# DISPLAYPORT_USBC.net
KiCad netlist of a schematic drawn in Altium Designer
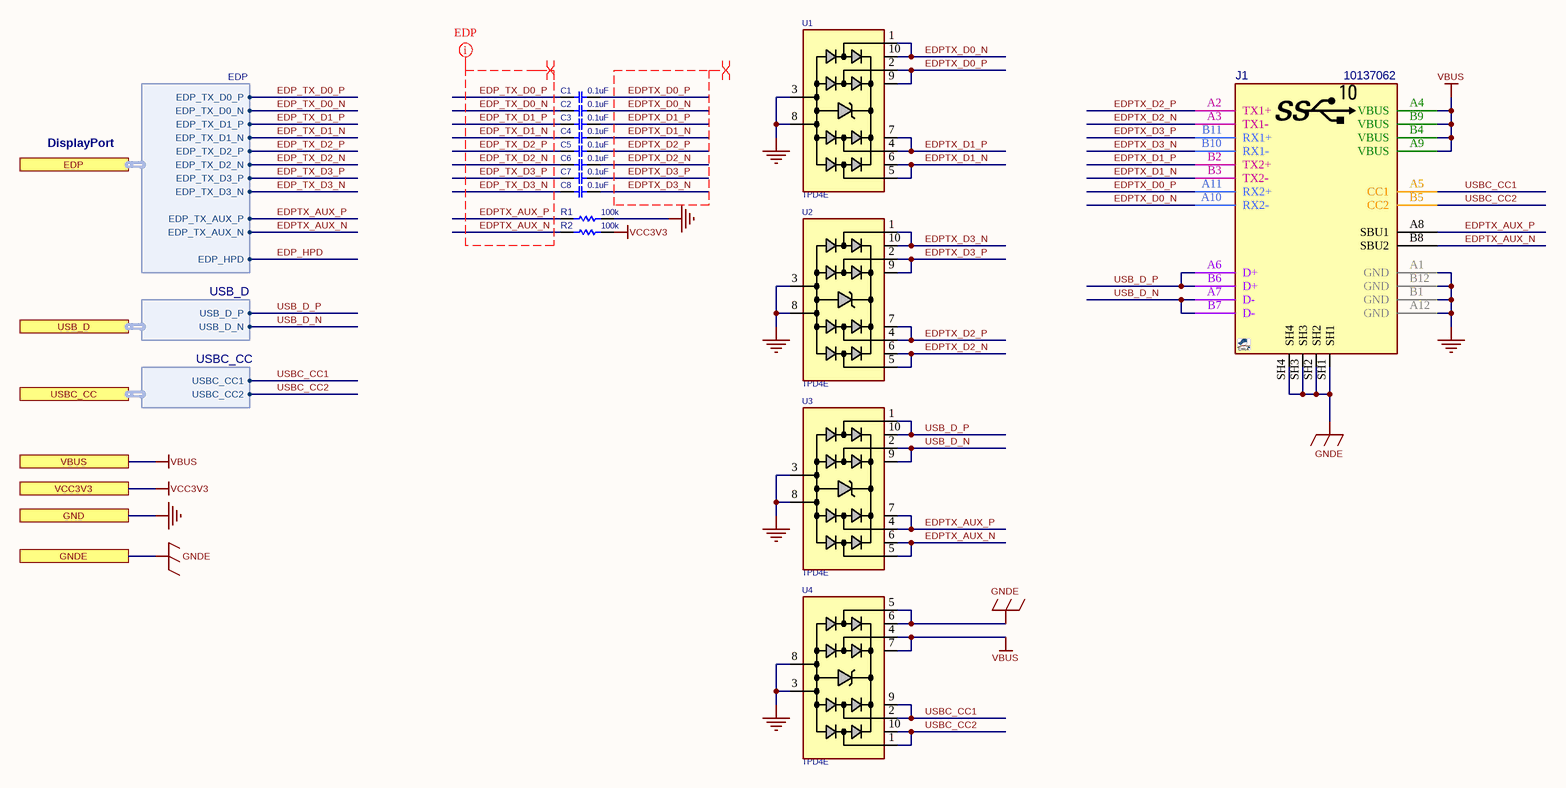
[diagram p0: DISPLAYPORT_USBC.SchDoc]

(export (version "E")
  (design (tool "Eeschema 10.0.6"))
  (components
    (comp (ref "C1")
      (value "0.1uF")
      (footprint "C0402O2")
      (description "CAP, MLCC")
      (fields (field (name "MANF_P#") "GRM155R61E104") (field (name "MANF") "Murata"))
      (libsource (lib "passive_smd") (part "CAP_SMD_MLCC"))
    )
    (comp (ref "C2")
      (value "0.1uF")
      (footprint "C0402O2")
      (description "CAP, MLCC")
      (fields (field (name "MANF_P#") "GRM155R61E104") (field (name "MANF") "Murata"))
      (libsource (lib "passive_smd") (part "CAP_SMD_MLCC"))
    )
    (comp (ref "C3")
      (value "0.1uF")
      (footprint "C0402O2")
      (description "CAP, MLCC")
      (fields (field (name "MANF_P#") "GRM155R61E104") (field (name "MANF") "Murata"))
      (libsource (lib "passive_smd") (part "CAP_SMD_MLCC"))
    )
    (comp (ref "C4")
      (value "0.1uF")
      (footprint "C0402O2")
      (description "CAP, MLCC")
      (fields (field (name "MANF_P#") "GRM155R61E104") (field (name "MANF") "Murata"))
      (libsource (lib "passive_smd") (part "CAP_SMD_MLCC"))
    )
    (comp (ref "C5")
      (value "0.1uF")
      (footprint "C0402O2")
      (description "CAP, MLCC")
      (fields (field (name "MANF_P#") "GRM155R61E104") (field (name "MANF") "Murata"))
      (libsource (lib "passive_smd") (part "CAP_SMD_MLCC"))
    )
    (comp (ref "C6")
      (value "0.1uF")
      (footprint "C0402O2")
      (description "CAP, MLCC")
      (fields (field (name "MANF_P#") "GRM155R61E104") (field (name "MANF") "Murata"))
      (libsource (lib "passive_smd") (part "CAP_SMD_MLCC"))
    )
    (comp (ref "C7")
      (value "0.1uF")
      (footprint "C0402O2")
      (description "CAP, MLCC")
      (fields (field (name "MANF_P#") "GRM155R61E104") (field (name "MANF") "Murata"))
      (libsource (lib "passive_smd") (part "CAP_SMD_MLCC"))
    )
    (comp (ref "C8")
      (value "0.1uF")
      (footprint "C0402O2")
      (description "CAP, MLCC")
      (fields (field (name "MANF_P#") "GRM155R61E104") (field (name "MANF") "Murata"))
      (libsource (lib "passive_smd") (part "CAP_SMD_MLCC"))
    )
    (comp (ref "J1")
      (value "10137062")
      (footprint "USBC_HYB_10137062")
      (description "CONN, USB, Type C, USB 3.1 Gen 1, Right-Angle, HYBRID")
      (fields (field (name "MANF") "Amphenol") (field (name "MANF_P#") "10137062-00021LF"))
      (libsource (lib "conn_usbc") (part "CONN_USBC_HYB_10137062"))
    )
    (comp (ref "R1")
      (value "100k")
      (footprint "R0402")
      (description "RESISTOR, SMD")
      (libsource (lib "passive_res_smd") (part "RES_SMD"))
    )
    (comp (ref "R2")
      (value "100k")
      (footprint "R0402")
      (description "RESISTOR, SMD")
      (libsource (lib "passive_res_smd") (part "RES_SMD"))
    )
    (comp (ref "U1")
      (value "TPD4E")
      (footprint "SON50_10_2510")
      (description "TVS, ESD PROTECT, 4CH,")
      (fields (field (name "MANF_P#") "TPD4E05U06DQA") (field (name "MANF") "Texas Instruments"))
      (libsource (lib "protect_tvs_esd_fuse") (part "TVS_X4_TPD4E05U06"))
    )
    (comp (ref "U2")
      (value "TPD4E")
      (footprint "SON50_10_2510")
      (description "TVS, ESD PROTECT, 4CH,")
      (fields (field (name "MANF_P#") "TPD4E05U06DQA") (field (name "MANF") "Texas Instruments"))
      (libsource (lib "protect_tvs_esd_fuse") (part "TVS_X4_TPD4E05U06"))
    )
    (comp (ref "U3")
      (value "TPD4E")
      (footprint "SON50_10_2510")
      (description "TVS, ESD PROTECT, 4CH,")
      (fields (field (name "MANF_P#") "TPD4E05U06DQA") (field (name "MANF") "Texas Instruments"))
      (libsource (lib "protect_tvs_esd_fuse") (part "TVS_X4_TPD4E05U06"))
    )
    (comp (ref "U4")
      (value "TPD4E")
      (footprint "SON50_10_2510")
      (description "TVS, ESD PROTECT, 4CH,")
      (fields (field (name "MANF_P#") "TPD4E05U06DQA") (field (name "MANF") "Texas Instruments"))
      (libsource (lib "protect_tvs_esd_fuse") (part "TVS_X4_TPD4E05U06"))
    )
  )
  (nets
    (net (code "4") (name "/EDPTX_AUX_N") (class "Default")
      (node (ref "J1") (pin "B8") (pinfunction "SBU2_B8") (pintype "passive"))
      (node (ref "R2") (pin "2") (pinfunction "2_2") (pintype "passive"))
      (node (ref "U3") (pin "5") (pinfunction "5_5") (pintype "passive"))
      (node (ref "U3") (pin "6") (pinfunction "6_6") (pintype "passive"))
    )
    (net (code "5") (name "/EDPTX_AUX_P") (class "Default")
      (node (ref "J1") (pin "A8") (pinfunction "SBU1_A8") (pintype "passive"))
      (node (ref "R1") (pin "2") (pinfunction "2_2") (pintype "passive"))
      (node (ref "U3") (pin "4") (pinfunction "4_4") (pintype "passive"))
      (node (ref "U3") (pin "7") (pinfunction "7_7") (pintype "passive"))
    )
    (net (code "6") (name "/EDPTX_D0_N") (class "Default")
      (node (ref "C2") (pin "2") (pinfunction "2_2") (pintype "passive"))
      (node (ref "J1") (pin "A10") (pinfunction "RX2-_A10") (pintype "passive"))
      (node (ref "U1") (pin "1") (pinfunction "1_1") (pintype "passive"))
      (node (ref "U1") (pin "10") (pinfunction "10_10") (pintype "passive"))
    )
    (net (code "7") (name "/EDPTX_D0_P") (class "Default")
      (node (ref "C1") (pin "2") (pinfunction "2_2") (pintype "passive"))
      (node (ref "J1") (pin "A11") (pinfunction "RX2+_A11") (pintype "passive"))
      (node (ref "U1") (pin "2") (pinfunction "2_2") (pintype "passive"))
      (node (ref "U1") (pin "9") (pinfunction "9_9") (pintype "passive"))
    )
    (net (code "8") (name "/EDPTX_D1_N") (class "Default")
      (node (ref "C4") (pin "2") (pinfunction "2_2") (pintype "passive"))
      (node (ref "J1") (pin "B3") (pinfunction "TX2-_B3") (pintype "passive"))
      (node (ref "U1") (pin "5") (pinfunction "5_5") (pintype "passive"))
      (node (ref "U1") (pin "6") (pinfunction "6_6") (pintype "passive"))
    )
    (net (code "9") (name "/EDPTX_D1_P") (class "Default")
      (node (ref "C3") (pin "2") (pinfunction "2_2") (pintype "passive"))
      (node (ref "J1") (pin "B2") (pinfunction "TX2+_B2") (pintype "passive"))
      (node (ref "U1") (pin "4") (pinfunction "4_4") (pintype "passive"))
      (node (ref "U1") (pin "7") (pinfunction "7_7") (pintype "passive"))
    )
    (net (code "10") (name "/EDPTX_D2_N") (class "Default")
      (node (ref "C6") (pin "2") (pinfunction "2_2") (pintype "passive"))
      (node (ref "J1") (pin "A3") (pinfunction "TX1-_A3") (pintype "passive"))
      (node (ref "U2") (pin "5") (pinfunction "5_5") (pintype "passive"))
      (node (ref "U2") (pin "6") (pinfunction "6_6") (pintype "passive"))
    )
    (net (code "11") (name "/EDPTX_D2_P") (class "Default")
      (node (ref "C5") (pin "2") (pinfunction "2_2") (pintype "passive"))
      (node (ref "J1") (pin "A2") (pinfunction "TX1+_A2") (pintype "passive"))
      (node (ref "U2") (pin "4") (pinfunction "4_4") (pintype "passive"))
      (node (ref "U2") (pin "7") (pinfunction "7_7") (pintype "passive"))
    )
    (net (code "12") (name "/EDPTX_D3_N") (class "Default")
      (node (ref "C8") (pin "2") (pinfunction "2_2") (pintype "passive"))
      (node (ref "J1") (pin "B10") (pinfunction "RX1-_B10") (pintype "passive"))
      (node (ref "U2") (pin "1") (pinfunction "1_1") (pintype "passive"))
      (node (ref "U2") (pin "10") (pinfunction "10_10") (pintype "passive"))
    )
    (net (code "13") (name "/EDPTX_D3_P") (class "Default")
      (node (ref "C7") (pin "2") (pinfunction "2_2") (pintype "passive"))
      (node (ref "J1") (pin "B11") (pinfunction "RX1+_B11") (pintype "passive"))
      (node (ref "U2") (pin "2") (pinfunction "2_2") (pintype "passive"))
      (node (ref "U2") (pin "9") (pinfunction "9_9") (pintype "passive"))
    )
    (net (code "15") (name "/EDP_TX_D0_N") (class "Default")
      (node (ref "C2") (pin "1") (pinfunction "1_1") (pintype "passive"))
    )
    (net (code "16") (name "/EDP_TX_D0_P") (class "Default")
      (node (ref "C1") (pin "1") (pinfunction "1_1") (pintype "passive"))
    )
    (net (code "17") (name "/EDP_TX_D1_N") (class "Default")
      (node (ref "C4") (pin "1") (pinfunction "1_1") (pintype "passive"))
    )
    (net (code "18") (name "/EDP_TX_D1_P") (class "Default")
      (node (ref "C3") (pin "1") (pinfunction "1_1") (pintype "passive"))
    )
    (net (code "19") (name "/EDP_TX_D2_N") (class "Default")
      (node (ref "C6") (pin "1") (pinfunction "1_1") (pintype "passive"))
    )
    (net (code "20") (name "/EDP_TX_D2_P") (class "Default")
      (node (ref "C5") (pin "1") (pinfunction "1_1") (pintype "passive"))
    )
    (net (code "21") (name "/EDP_TX_D3_N") (class "Default")
      (node (ref "C8") (pin "1") (pinfunction "1_1") (pintype "passive"))
    )
    (net (code "22") (name "/EDP_TX_D3_P") (class "Default")
      (node (ref "C7") (pin "1") (pinfunction "1_1") (pintype "passive"))
    )
    (net (code "23") (name "/USBC_CC1") (class "Default")
      (node (ref "J1") (pin "A5") (pinfunction "CC1_A5") (pintype "passive"))
      (node (ref "U4") (pin "2") (pinfunction "2_2") (pintype "passive"))
      (node (ref "U4") (pin "9") (pinfunction "9_9") (pintype "passive"))
    )
    (net (code "24") (name "/USBC_CC2") (class "Default")
      (node (ref "J1") (pin "B5") (pinfunction "CC2_B5") (pintype "passive"))
      (node (ref "U4") (pin "1") (pinfunction "1_1") (pintype "passive"))
      (node (ref "U4") (pin "10") (pinfunction "10_10") (pintype "passive"))
    )
    (net (code "25") (name "/USB_D_N") (class "Default")
      (node (ref "J1") (pin "A7") (pinfunction "D-_A7") (pintype "passive"))
      (node (ref "J1") (pin "B7") (pinfunction "D-_B7") (pintype "passive"))
      (node (ref "U3") (pin "2") (pinfunction "2_2") (pintype "passive"))
      (node (ref "U3") (pin "9") (pinfunction "9_9") (pintype "passive"))
    )
    (net (code "26") (name "/USB_D_P") (class "Default")
      (node (ref "J1") (pin "A6") (pinfunction "D+_A6") (pintype "passive"))
      (node (ref "J1") (pin "B6") (pinfunction "D+_B6") (pintype "passive"))
      (node (ref "U3") (pin "1") (pinfunction "1_1") (pintype "passive"))
      (node (ref "U3") (pin "10") (pinfunction "10_10") (pintype "passive"))
    )
    (net (code "30") (name "GND") (class "Default")
      (node (ref "J1") (pin "A1") (pinfunction "GND_A1") (pintype "passive"))
      (node (ref "J1") (pin "A12") (pinfunction "GND_A12") (pintype "passive"))
      (node (ref "J1") (pin "B1") (pinfunction "GND_B1") (pintype "passive"))
      (node (ref "J1") (pin "B12") (pinfunction "GND_B12") (pintype "passive"))
      (node (ref "R1") (pin "1") (pinfunction "1_1") (pintype "passive"))
      (node (ref "U1") (pin "3") (pinfunction "3_3") (pintype "passive"))
      (node (ref "U1") (pin "8") (pinfunction "8_8") (pintype "passive"))
      (node (ref "U2") (pin "3") (pinfunction "3_3") (pintype "passive"))
      (node (ref "U2") (pin "8") (pinfunction "8_8") (pintype "passive"))
      (node (ref "U3") (pin "3") (pinfunction "3_3") (pintype "passive"))
      (node (ref "U3") (pin "8") (pinfunction "8_8") (pintype "passive"))
      (node (ref "U4") (pin "3") (pinfunction "3_3") (pintype "passive"))
      (node (ref "U4") (pin "8") (pinfunction "8_8") (pintype "passive"))
    )
    (net (code "31") (name "GNDE") (class "Default")
      (node (ref "J1") (pin "SH1") (pinfunction "SH1_SH1") (pintype "passive"))
      (node (ref "J1") (pin "SH2") (pinfunction "SH2_SH2") (pintype "passive"))
      (node (ref "J1") (pin "SH3") (pinfunction "SH3_SH3") (pintype "passive"))
      (node (ref "J1") (pin "SH4") (pinfunction "SH4_SH4") (pintype "passive"))
      (node (ref "U4") (pin "5") (pinfunction "5_5") (pintype "passive"))
      (node (ref "U4") (pin "6") (pinfunction "6_6") (pintype "passive"))
    )
    (net (code "32") (name "VBUS") (class "Default")
      (node (ref "J1") (pin "A4") (pinfunction "VBUS_A4") (pintype "passive"))
      (node (ref "J1") (pin "A9") (pinfunction "VBUS_A9") (pintype "passive"))
      (node (ref "J1") (pin "B4") (pinfunction "VBUS_B4") (pintype "passive"))
      (node (ref "J1") (pin "B9") (pinfunction "VBUS_B9") (pintype "passive"))
      (node (ref "U4") (pin "4") (pinfunction "4_4") (pintype "passive"))
      (node (ref "U4") (pin "7") (pinfunction "7_7") (pintype "passive"))
    )
    (net (code "33") (name "VCC3V3") (class "Default")
      (node (ref "R2") (pin "1") (pinfunction "1_1") (pintype "passive"))
    )
  )
)
